# cpupwrbackup.net
KiCad netlist of a schematic drawn in Altium Designer
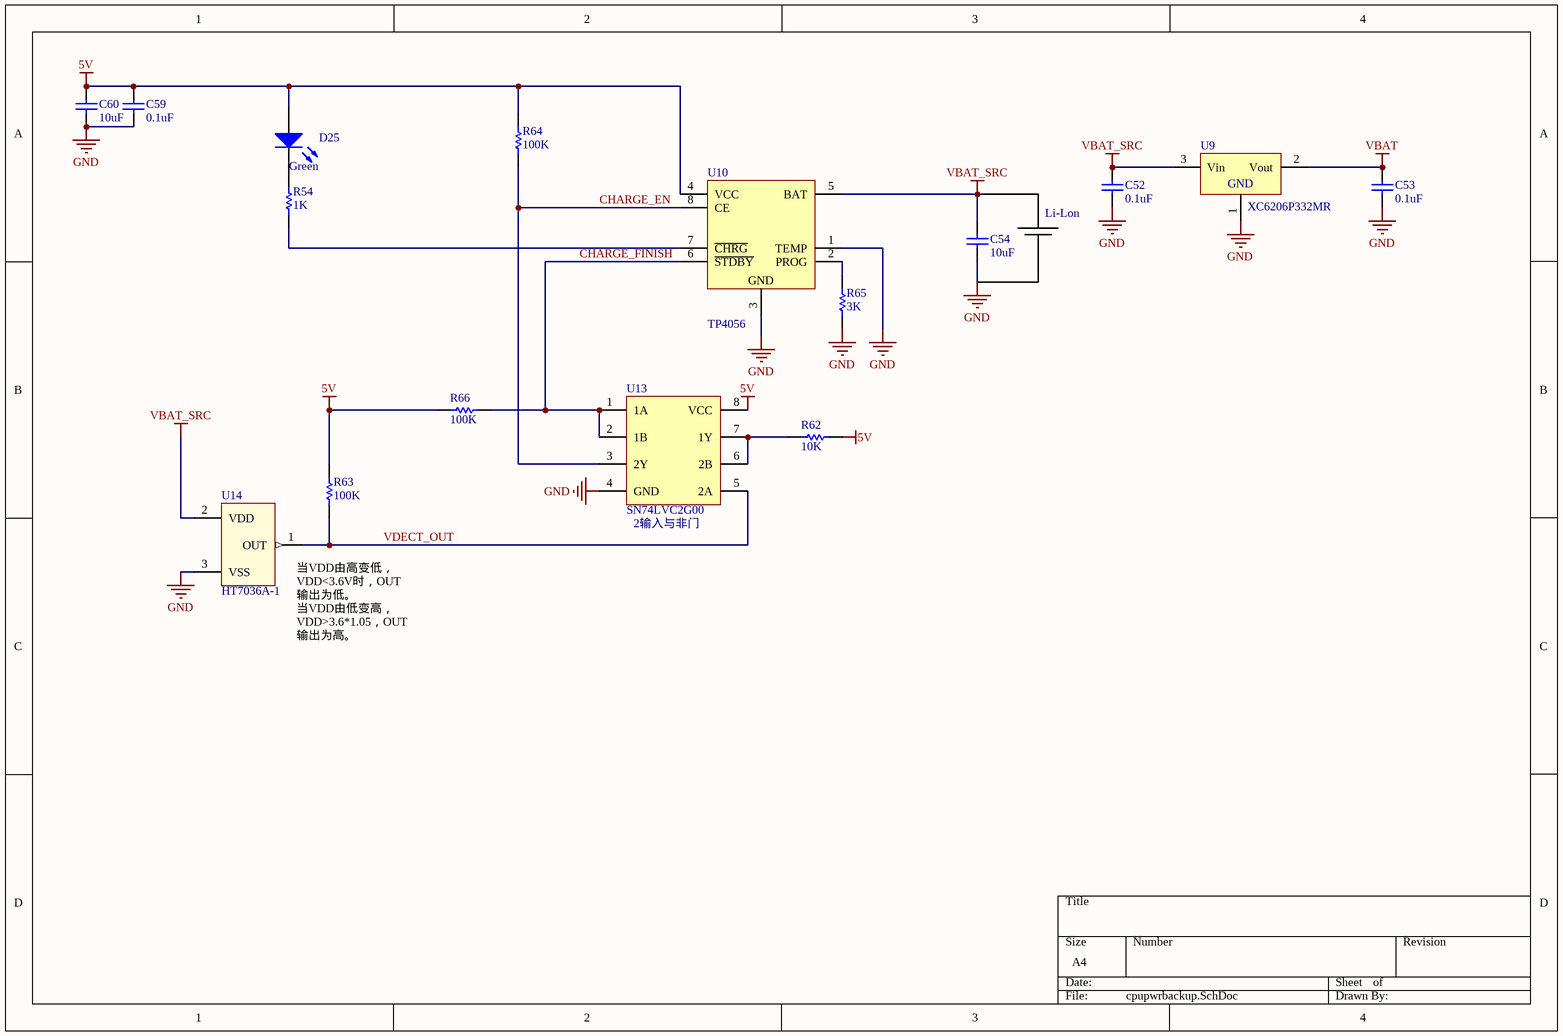
[diagram p0: cpupwrbackup.SchDoc]

(export (version "E")
  (design (tool "Eeschema 10.0.6"))
  (components
    (comp (ref "C52")
      (value "0.1uF")
      (footprint "CAPC2012M")
      (description "Capacitor")
      (fields (field (name "PUBLISHER") "Altium Limited"))
      (libsource (lib "Miscellaneous Devices") (part "Cap"))
    )
    (comp (ref "C53")
      (value "0.1uF")
      (footprint "CAPC2012M")
      (description "Capacitor")
      (fields (field (name "PUBLISHER") "Altium Limited"))
      (libsource (lib "Miscellaneous Devices") (part "Cap"))
    )
    (comp (ref "C54")
      (value "10uF")
      (footprint "CAPC2012M")
      (description "Capacitor")
      (fields (field (name "PUBLISHER") "Altium Limited"))
      (libsource (lib "Miscellaneous Devices") (part "Cap"))
    )
    (comp (ref "C59")
      (value "0.1uF")
      (footprint "CAPC2012M")
      (description "Capacitor")
      (fields (field (name "PUBLISHER") "Altium Limited"))
      (libsource (lib "Miscellaneous Devices") (part "Cap"))
    )
    (comp (ref "C60")
      (value "10uF")
      (footprint "CAPC2012M")
      (description "Capacitor")
      (fields (field (name "PUBLISHER") "Altium Limited"))
      (libsource (lib "Miscellaneous Devices") (part "Cap"))
    )
    (comp (ref "D25")
      (value "Green")
      (footprint "CD2012-0805")
      (description "Green LED,Output indicate.")
      (fields (field (name "PUBLISHER") "Altium Limited"))
      (libsource (lib "Miscellaneous Devices") (part "LED1"))
    )
    (comp (ref "R54")
      (value "1K")
      (footprint "RESC2012M")
      (description "Resistor")
      (fields (field (name "PUBLISHER") "Altium Limited"))
      (libsource (lib "Miscellaneous Devices") (part "Res1"))
    )
    (comp (ref "R62")
      (value "10K")
      (footprint "RESC2012M")
      (description "Resistor")
      (fields (field (name "PUBLISHER") "Altium Limited"))
      (libsource (lib "Miscellaneous Devices") (part "Res1"))
    )
    (comp (ref "R63")
      (value "100K")
      (footprint "RESC2012M")
      (description "Resistor")
      (fields (field (name "PUBLISHER") "Altium Limited"))
      (libsource (lib "Miscellaneous Devices") (part "Res1"))
    )
    (comp (ref "R64")
      (value "100K")
      (footprint "RESC2012M")
      (description "Resistor")
      (fields (field (name "PUBLISHER") "Altium Limited"))
      (libsource (lib "Miscellaneous Devices") (part "Res1"))
    )
    (comp (ref "R65")
      (value "3K")
      (footprint "RESC2012M")
      (description "Resistor")
      (fields (field (name "PUBLISHER") "Altium Limited"))
      (libsource (lib "Miscellaneous Devices") (part "Res1"))
    )
    (comp (ref "R66")
      (value "100K")
      (footprint "RESC2012M")
      (description "Resistor")
      (fields (field (name "PUBLISHER") "Altium Limited"))
      (libsource (lib "Miscellaneous Devices") (part "Res1"))
    )
    (comp (ref "U9")
      (value "XC6206P332MR")
      (footprint "SOT-23_M")
      (description "250mA Low ESR Dropout Linear Regulator")
      (libsource (lib "UserSchDev") (part "XC6206"))
    )
    (comp (ref "U10")
      (value "TP4056")
      (footprint "NSO8_TP4056")
      (description "锂电池充电管理")
      (libsource (lib "UserSchDev") (part "TP4056"))
    )
    (comp (ref "U13")
      (value "SN74LVC2G00")
      (footprint "PDSO-G8")
      (description "Dual 2-input positive-NAND gate")
      (libsource (lib "UserSchDev") (part "SN74LVC2G00"))
    )
    (comp (ref "U14") (value "HT7036A-1") (footprint "SOT89M") (libsource (lib "UserSchDev") (part "HT70XX")))
  )
  (nets
    (net (code "1") (name "/CHARGE_EN") (class "Default")
      (node (ref "R64") (pin "1") (pinfunction "1_1") (pintype "passive"))
      (node (ref "U10") (pin "8") (pinfunction "CE_8") (pintype "passive"))
      (node (ref "U13") (pin "3") (pinfunction "2Y_3") (pintype "passive"))
    )
    (net (code "2") (name "/CHARGE_FINISH") (class "Default")
      (node (ref "R66") (pin "1") (pinfunction "1_1") (pintype "passive"))
      (node (ref "U10") (pin "6") (pinfunction "~{STDBY}_6") (pintype "passive"))
      (node (ref "U13") (pin "1") (pinfunction "1A_1") (pintype "passive"))
      (node (ref "U13") (pin "2") (pinfunction "1B_2") (pintype "passive"))
    )
    (net (code "3") (name "/VDECT_OUT") (class "Default")
      (node (ref "R63") (pin "1") (pinfunction "1_1") (pintype "passive"))
      (node (ref "U13") (pin "5") (pinfunction "2A_5") (pintype "passive"))
      (node (ref "U14") (pin "1") (pinfunction "OUT_1") (pintype "output"))
    )
    (net (code "4") (name "5V") (class "Default")
      (node (ref "C59") (pin "1") (pinfunction "1_1") (pintype "passive"))
      (node (ref "C60") (pin "1") (pinfunction "1_1") (pintype "passive"))
      (node (ref "D25") (pin "1") (pinfunction "A_1") (pintype "passive"))
      (node (ref "R62") (pin "1") (pinfunction "1_1") (pintype "passive"))
      (node (ref "R63") (pin "2") (pinfunction "2_2") (pintype "passive"))
      (node (ref "R64") (pin "2") (pinfunction "2_2") (pintype "passive"))
      (node (ref "R66") (pin "2") (pinfunction "2_2") (pintype "passive"))
      (node (ref "U10") (pin "4") (pinfunction "VCC_4") (pintype "passive"))
      (node (ref "U13") (pin "8") (pinfunction "VCC_8") (pintype "passive"))
    )
    (net (code "5") (name "GND") (class "Default")
      (node (ref "C52") (pin "2") (pinfunction "2_2") (pintype "passive"))
      (node (ref "C53") (pin "2") (pinfunction "2_2") (pintype "passive"))
      (node (ref "C54") (pin "2") (pinfunction "2_2") (pintype "passive"))
      (node (ref "C59") (pin "2") (pinfunction "2_2") (pintype "passive"))
      (node (ref "C60") (pin "2") (pinfunction "2_2") (pintype "passive"))
      (node (ref "R65") (pin "1") (pinfunction "1_1") (pintype "passive"))
      (node (ref "U10") (pin "1") (pinfunction "TEMP_1") (pintype "passive"))
      (node (ref "U10") (pin "3") (pinfunction "GND_3") (pintype "passive"))
      (node (ref "U13") (pin "4") (pinfunction "GND_4") (pintype "passive"))
      (node (ref "U14") (pin "3") (pinfunction "VSS_3") (pintype "power_in"))
      (node (ref "U9") (pin "1") (pinfunction "GND_1") (pintype "passive"))
    )
    (net (code "6") (name "Net-(D25-K)") (class "Default")
      (node (ref "D25") (pin "2") (pinfunction "K_2") (pintype "passive"))
      (node (ref "R54") (pin "1") (pinfunction "1_1") (pintype "passive"))
    )
    (net (code "7") (name "Net-(U10-PROG)") (class "Default")
      (node (ref "R65") (pin "2") (pinfunction "2_2") (pintype "passive"))
      (node (ref "U10") (pin "2") (pinfunction "PROG_2") (pintype "passive"))
    )
    (net (code "8") (name "Net-(U10-~{CHRG})") (class "Default")
      (node (ref "R54") (pin "2") (pinfunction "2_2") (pintype "passive"))
      (node (ref "U10") (pin "7") (pinfunction "~{CHRG}_7") (pintype "passive"))
    )
    (net (code "9") (name "Net-(U13-1Y)") (class "Default")
      (node (ref "R62") (pin "2") (pinfunction "2_2") (pintype "passive"))
      (node (ref "U13") (pin "6") (pinfunction "2B_6") (pintype "passive"))
      (node (ref "U13") (pin "7") (pinfunction "1Y_7") (pintype "passive"))
    )
    (net (code "10") (name "VBAT") (class "Default")
      (node (ref "C53") (pin "1") (pinfunction "1_1") (pintype "passive"))
      (node (ref "U9") (pin "2") (pinfunction "Vout_2") (pintype "passive"))
    )
    (net (code "11") (name "VBAT_SRC") (class "Default")
      (node (ref "C52") (pin "1") (pinfunction "1_1") (pintype "passive"))
      (node (ref "C54") (pin "1") (pinfunction "1_1") (pintype "passive"))
      (node (ref "U10") (pin "5") (pinfunction "BAT_5") (pintype "passive"))
      (node (ref "U14") (pin "2") (pinfunction "VDD_2") (pintype "power_in"))
      (node (ref "U9") (pin "3") (pinfunction "Vin_3") (pintype "passive"))
    )
  )
)
